# CAN.net
KiCad netlist of a schematic drawn in Altium Designer
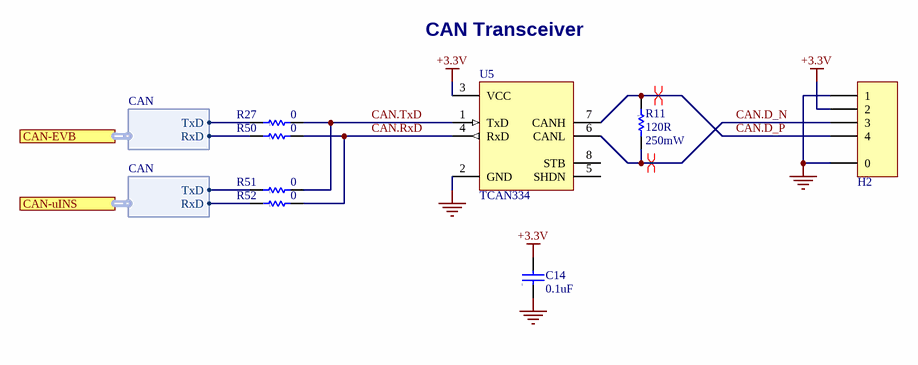
[diagram p0: CAN.SchDoc]

(export (version "E")
  (design (tool "Eeschema 10.0.6"))
  (components
    (comp (ref "C14")
      (value "0.1uF")
      (footprint "0402")
      (description "CAP CER .10UF 50V X7R 10% 0402")
      (fields
        (field (name "MANUFACTURER") "TDK Corporation")
        (field (name "MANUFACTURER PART NUMBER") "C1005X7R1H104K")
        (field (name "PUBLISHER") "Altium Limited")
      )
      (libsource (lib "General") (part "Cap"))
    )
    (comp (ref "H2")
      (value "Hdr - 4pin - mount")
      (footprint "SM04B-GHS-TB(LF)(SN)")
      (description "CONN HEADER GH SIDE 4POS 1.25MM")
      (fields
        (field (name "MANUFACTURER") "JST")
        (field (name "MANUFACTURER PART NUMBER") "SM04B-GHS-TB(LF)(SN)-")
      )
      (libsource (lib "Connectors") (part "Hdr - 4pin - mount"))
    )
    (comp (ref "R11")
      (value "120R")
      (footprint "R0603")
      (description "RES SMD 120 OHM 5% 1/4W 0603")
      (fields
        (field (name "MANUFACTURER") "Rohm")
        (field (name "MANUFACTURER PART NUMBER") "ESR03EZPJ121")
        (field (name "MAX POWER DISSIPATION") "250mW")
      )
      (libsource (lib "General") (part "Res"))
    )
    (comp (ref "R27")
      (value "0")
      (footprint "R0402")
      (description "RES SMD 0 OHM JUMPER 1/16W 0402")
      (fields
        (field (name "MANUFACTURER") "Yageo")
        (field (name "MANUFACTURER PART NUMBER") "RC0402JR-070RL")
      )
      (libsource (lib "General") (part "Res"))
    )
    (comp (ref "R50")
      (value "0")
      (footprint "R0402")
      (description "RES SMD 0 OHM JUMPER 1/16W 0402")
      (fields
        (field (name "MANUFACTURER") "Yageo")
        (field (name "MANUFACTURER PART NUMBER") "RC0402JR-070RL")
      )
      (libsource (lib "General") (part "Res"))
    )
    (comp (ref "R51")
      (value "0")
      (footprint "R0402")
      (description "RES SMD 0 OHM JUMPER 1/16W 0402")
      (fields
        (field (name "MANUFACTURER") "Yageo")
        (field (name "MANUFACTURER PART NUMBER") "RC0402JR-070RL")
      )
      (libsource (lib "General") (part "Res"))
    )
    (comp (ref "R52")
      (value "0")
      (footprint "R0402")
      (description "RES SMD 0 OHM JUMPER 1/16W 0402")
      (fields
        (field (name "MANUFACTURER") "Yageo")
        (field (name "MANUFACTURER PART NUMBER") "RC0402JR-070RL")
      )
      (libsource (lib "General") (part "Res"))
    )
    (comp (ref "U5")
      (value "TCAN334")
      (footprint "SOT23-8-65P280X145-8N")
      (description "IC TXRX CAN 3.3V SOT23-8")
      (fields
        (field (name "MANUFACTURER") "Texas Instruments")
        (field (name "MANUFACTURER PART NUMBER") "TCAN334DCNR")
      )
      (libsource (lib "ICs") (part "TCAN334"))
    )
  )
  (nets
    (net (code "2") (name "+3.3V") (class "Default")
      (node (ref "C14") (pin "2") (pinfunction "2_2") (pintype "passive"))
      (node (ref "H2") (pin "2") (pinfunction "2_2") (pintype "passive"))
      (node (ref "U5") (pin "3") (pinfunction "VCC_3") (pintype "power_in"))
    )
    (net (code "3") (name "/CAN.D_N") (class "Default")
      (node (ref "H2") (pin "3") (pinfunction "3_3") (pintype "passive"))
      (node (ref "R11") (pin "2") (pinfunction "2_2") (pintype "passive"))
      (node (ref "U5") (pin "6") (pinfunction "CANL_6") (pintype "passive"))
    )
    (net (code "4") (name "/CAN.D_P") (class "Default")
      (node (ref "H2") (pin "4") (pinfunction "4_4") (pintype "passive"))
      (node (ref "R11") (pin "1") (pinfunction "1_1") (pintype "passive"))
      (node (ref "U5") (pin "7") (pinfunction "CANH_7") (pintype "passive"))
    )
    (net (code "5") (name "/CAN.RxD") (class "Default")
      (node (ref "R50") (pin "2") (pinfunction "2_2") (pintype "passive"))
      (node (ref "R52") (pin "2") (pinfunction "2_2") (pintype "passive"))
      (node (ref "U5") (pin "4") (pinfunction "RxD_4") (pintype "output"))
    )
    (net (code "6") (name "/CAN.TxD") (class "Default")
      (node (ref "R27") (pin "2") (pinfunction "2_2") (pintype "passive"))
      (node (ref "R51") (pin "2") (pinfunction "2_2") (pintype "passive"))
      (node (ref "U5") (pin "1") (pinfunction "TxD_1") (pintype "input"))
    )
    (net (code "8") (name "GND") (class "Default")
      (node (ref "C14") (pin "1") (pinfunction "1_1") (pintype "passive"))
      (node (ref "H2") (pin "0") (pinfunction "0_0") (pintype "passive"))
      (node (ref "H2") (pin "1") (pinfunction "1_1") (pintype "passive"))
      (node (ref "U5") (pin "2") (pinfunction "GND_2") (pintype "power_in"))
    )
    (net (code "9") (name "unconnected-(R27-Pad1)") (class "Default")
      (node (ref "R27") (pin "1") (pinfunction "1_1") (pintype "passive"))
    )
    (net (code "10") (name "unconnected-(R50-Pad1)") (class "Default")
      (node (ref "R50") (pin "1") (pinfunction "1_1") (pintype "passive"))
    )
    (net (code "11") (name "unconnected-(R51-Pad1)") (class "Default")
      (node (ref "R51") (pin "1") (pinfunction "1_1") (pintype "passive"))
    )
    (net (code "12") (name "unconnected-(R52-Pad1)") (class "Default")
      (node (ref "R52") (pin "1") (pinfunction "1_1") (pintype "passive"))
    )
    (net (code "13") (name "unconnected-(U5-SHDN-Pad5)") (class "Default")
      (node (ref "U5") (pin "5") (pinfunction "SHDN_5") (pintype "passive"))
    )
    (net (code "14") (name "unconnected-(U5-STB-Pad8)") (class "Default")
      (node (ref "U5") (pin "8") (pinfunction "STB_8") (pintype "passive"))
    )
  )
)
